# CustomTP4056Module_SMD.net
KiCad netlist of a schematic drawn in Altium Designer
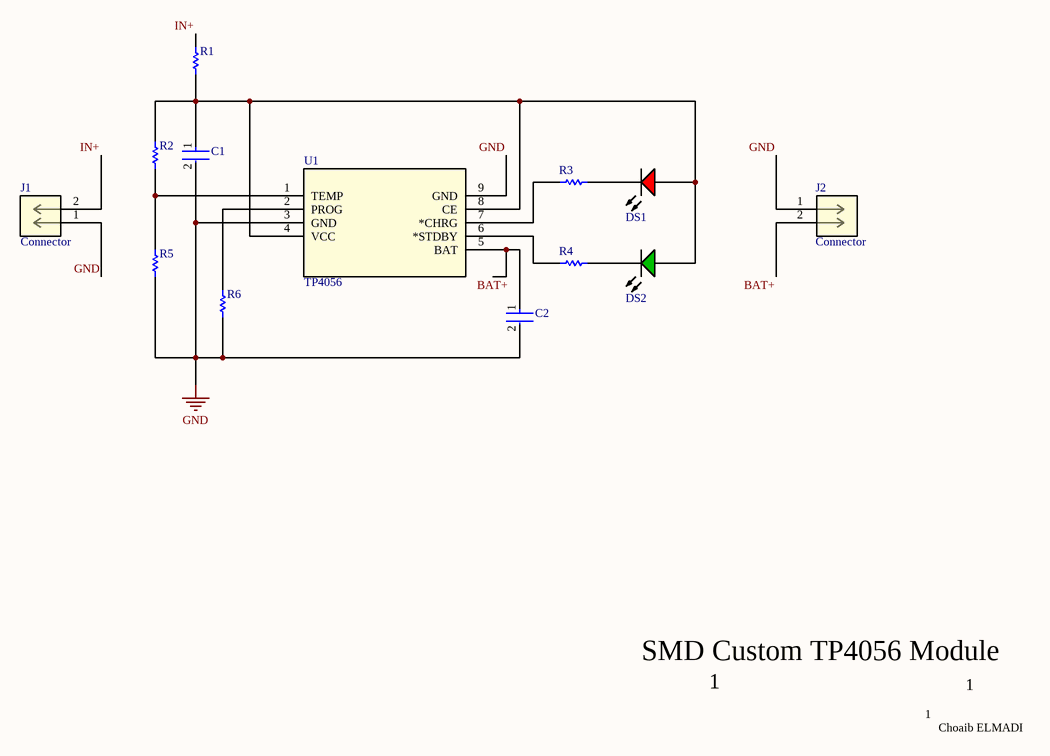
[diagram p0: CustomTP4056Module_SMD.SchDoc]

(export (version "E")
  (design (tool "Eeschema 10.0.6"))
  (components
    (comp (ref "C1")
      (value "1206ZC106KAT2A")
      (footprint "FP-1206-L_3_2_0_2-W_1_6_0-IPC_C")
      (description "General Purpose Ceramic Capacitor, 1206, 10uF, 10%, X7R, 15%, 10V")
      (fields (field (name "VOLTAGE") "10V") (field (name "TOLERANCE") "10%"))
      (libsource (lib "Altium Content Vault") (part "b4654b650e69147ec39a6b967a45e02"))
    )
    (comp (ref "C2")
      (value "1206ZC106KAT2A")
      (footprint "FP-1206-L_3_2_0_2-W_1_6_0-IPC_C")
      (description "General Purpose Ceramic Capacitor, 1206, 10uF, 10%, X7R, 15%, 10V")
      (fields (field (name "VOLTAGE") "10V") (field (name "TOLERANCE") "10%"))
      (libsource (lib "Altium Content Vault") (part "b4654b650e69147ec39a6b967a45e02"))
    )
    (comp (ref "DS1")
      (value "LTST-C170KRKT")
      (footprint "LTST-C170KRKT_V")
      (description "LED Red, 75 mW, 54 mcd, -55 to 85 degC, 2-Pin SMD, RoHS, Tape and Reel")
      (fields (field (name "MANUFACTURER") "Lite-On"))
      (libsource (lib "Altium Content Vault") (part "LED-RED-AK-2"))
    )
    (comp (ref "DS2")
      (value "LTST-C170KGKT")
      (footprint "LTST-LTST-C170KGKT-2_V")
      (description "Ultra Bright AlInGaP Chip LED, 75 mW, -55 to 85 degC, 2-Pin SMD (0805), RoHS, Tape and Reel")
      (fields (field (name "MANUFACTURER") "Lite-On"))
      (libsource (lib "Altium Content Vault") (part "LED-GREEN-KA-2"))
    )
    (comp (ref "J1")
      (value "Connector")
      (footprint "CONN_M20-99902_HRW")
      (description "No Description Available")
      (libsource (lib "") (part "M20-9990245_1"))
    )
    (comp (ref "J2")
      (value "Connector")
      (footprint "CONN_M20-99902_HRW")
      (description "No Description Available")
      (libsource (lib "M20-9990245") (part "M20-9990245"))
    )
    (comp (ref "R1")
      (value "ERA3AEB221V")
      (footprint "RESC1608X55X30LL20T20")
      (fields (field (name "MANUFACTURER") "Panasonic"))
      (libsource (lib "Altium Content Vault") (part "RES"))
    )
    (comp (ref "R2")
      (value "ERA3AEB221V")
      (footprint "RESC1608X55X30LL20T20")
      (fields (field (name "MANUFACTURER") "Panasonic"))
      (libsource (lib "Altium Content Vault") (part "RES"))
    )
    (comp (ref "R3")
      (value "ERA3AEB221V")
      (footprint "RESC1608X55X30LL20T20")
      (fields (field (name "MANUFACTURER") "Panasonic"))
      (libsource (lib "Altium Content Vault") (part "RES"))
    )
    (comp (ref "R4")
      (value "ERA3AEB221V")
      (footprint "RESC1608X55X30LL20T20")
      (fields (field (name "MANUFACTURER") "Panasonic"))
      (libsource (lib "Altium Content Vault") (part "RES"))
    )
    (comp (ref "R5")
      (value "ERA3AEB221V")
      (footprint "RESC1608X55X30LL20T20")
      (fields (field (name "MANUFACTURER") "Panasonic"))
      (libsource (lib "Altium Content Vault") (part "RES"))
    )
    (comp (ref "R6")
      (value "ERA3AEB221V")
      (footprint "RESC1608X55X30LL20T20")
      (fields (field (name "MANUFACTURER") "Panasonic"))
      (libsource (lib "Altium Content Vault") (part "RES"))
    )
    (comp (ref "U1")
      (value "TP4056")
      (footprint "ESOP8_TPW")
      (description "No Description Available")
      (libsource (lib "TP4056") (part "TP4056"))
    )
  )
  (nets
    (net (code "1") (name "/BAT+") (class "Default")
      (node (ref "C2") (pin "1") (pinfunction "1_1") (pintype "passive"))
      (node (ref "J2") (pin "2") (pinfunction "2_2") (pintype "passive"))
      (node (ref "U1") (pin "5") (pinfunction "BAT_5") (pintype "passive"))
    )
    (net (code "2") (name "/IN+") (class "Default")
      (node (ref "J1") (pin "2") (pinfunction "2_2") (pintype "passive"))
      (node (ref "R1") (pin "1") (pinfunction "1_1") (pintype "passive"))
    )
    (net (code "3") (name "GND") (class "Default")
      (node (ref "C1") (pin "2") (pinfunction "2_2") (pintype "passive"))
      (node (ref "C2") (pin "2") (pinfunction "2_2") (pintype "passive"))
      (node (ref "J1") (pin "1") (pinfunction "1_1") (pintype "passive"))
      (node (ref "J2") (pin "1") (pinfunction "1_1") (pintype "passive"))
      (node (ref "R5") (pin "1") (pinfunction "1_1") (pintype "passive"))
      (node (ref "R6") (pin "2") (pinfunction "2_2") (pintype "passive"))
      (node (ref "U1") (pin "3") (pinfunction "GND_3") (pintype "power_in"))
      (node (ref "U1") (pin "9") (pinfunction "GND_9") (pintype "power_in"))
    )
    (net (code "4") (name "Net-(DS1-A)") (class "Default")
      (node (ref "C1") (pin "1") (pinfunction "1_1") (pintype "passive"))
      (node (ref "DS1") (pin "1") (pinfunction "A_1") (pintype "passive"))
      (node (ref "DS2") (pin "2") (pinfunction "A_2") (pintype "passive"))
      (node (ref "R1") (pin "2") (pinfunction "2_2") (pintype "passive"))
      (node (ref "R2") (pin "2") (pinfunction "2_2") (pintype "passive"))
      (node (ref "U1") (pin "4") (pinfunction "VCC_4") (pintype "power_in"))
      (node (ref "U1") (pin "8") (pinfunction "CE_8") (pintype "passive"))
    )
    (net (code "5") (name "Net-(DS1-K)") (class "Default")
      (node (ref "DS1") (pin "2") (pinfunction "K_2") (pintype "passive"))
      (node (ref "R3") (pin "2") (pinfunction "2_2") (pintype "passive"))
    )
    (net (code "6") (name "Net-(DS2-K)") (class "Default")
      (node (ref "DS2") (pin "1") (pinfunction "K_1") (pintype "passive"))
      (node (ref "R4") (pin "2") (pinfunction "2_2") (pintype "passive"))
    )
    (net (code "7") (name "Net-(U1-*CHRG)") (class "Default")
      (node (ref "R3") (pin "1") (pinfunction "1_1") (pintype "passive"))
      (node (ref "U1") (pin "7") (pinfunction "*CHRG_7") (pintype "passive"))
    )
    (net (code "8") (name "Net-(U1-*STDBY)") (class "Default")
      (node (ref "R4") (pin "1") (pinfunction "1_1") (pintype "passive"))
      (node (ref "U1") (pin "6") (pinfunction "*STDBY_6") (pintype "passive"))
    )
    (net (code "9") (name "Net-(U1-PROG)") (class "Default")
      (node (ref "R6") (pin "1") (pinfunction "1_1") (pintype "passive"))
      (node (ref "U1") (pin "2") (pinfunction "PROG_2") (pintype "passive"))
    )
    (net (code "10") (name "Net-(U1-TEMP)") (class "Default")
      (node (ref "R2") (pin "1") (pinfunction "1_1") (pintype "passive"))
      (node (ref "R5") (pin "2") (pinfunction "2_2") (pintype "passive"))
      (node (ref "U1") (pin "1") (pinfunction "TEMP_1") (pintype "passive"))
    )
  )
)
